# BATTERIES_CONTROLLER.net
KiCad netlist of a schematic drawn in EAGLE
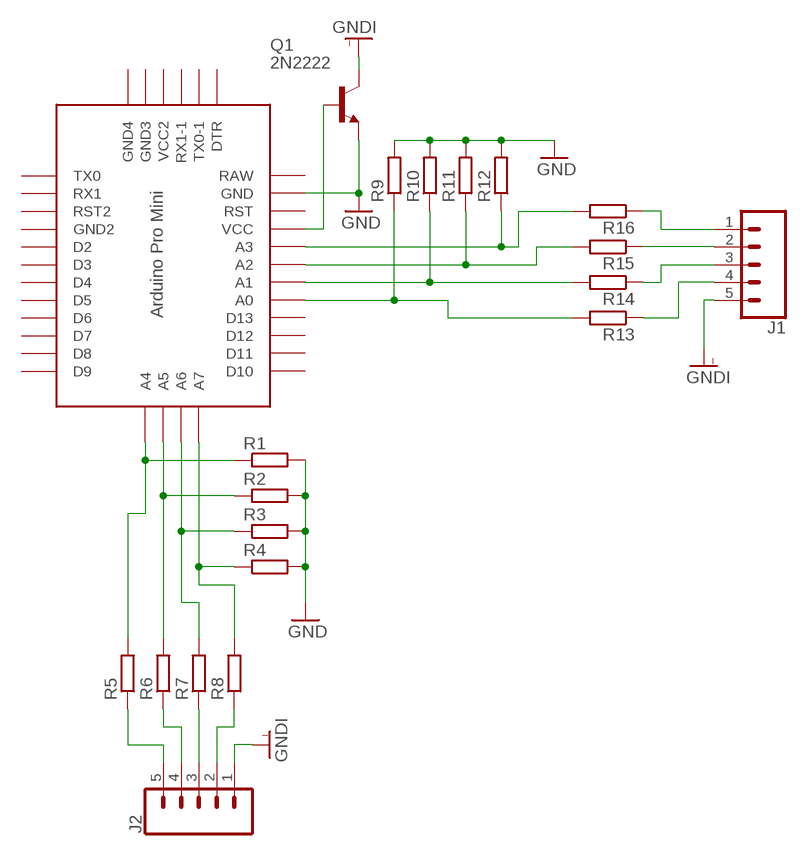
[diagram p0: schematic, sheet 1]

(export (version "E")
  (design (tool "Eeschema 10.0.6"))
  (components
    (comp (ref "J1")
      (value "CONN_05")
      (footprint "eagle-import:1X05")
      (libsource (lib "eagle-import") (part "CONN_05"))
    )
    (comp (ref "J2")
      (value "CONN_05")
      (footprint "eagle-import:1X05")
      (libsource (lib "eagle-import") (part "CONN_05"))
    )
    (comp (ref "Q1")
      (value "2N2222")
      (footprint "eagle-import:TO18")
      (libsource (lib "eagle-import") (part "2N2222"))
    )
    (comp (ref "R1")
      (value "R-EU_0204/7")
      (footprint "eagle-import:0204_7")
      (libsource (lib "eagle-import") (part "R-EU_0204/7"))
    )
    (comp (ref "R2")
      (value "R-EU_0204/7")
      (footprint "eagle-import:0204_7")
      (libsource (lib "eagle-import") (part "R-EU_0204/7"))
    )
    (comp (ref "R3")
      (value "R-EU_0204/7")
      (footprint "eagle-import:0204_7")
      (libsource (lib "eagle-import") (part "R-EU_0204/7"))
    )
    (comp (ref "R4")
      (value "R-EU_0204/7")
      (footprint "eagle-import:0204_7")
      (libsource (lib "eagle-import") (part "R-EU_0204/7"))
    )
    (comp (ref "R5")
      (value "R-EU_0204/7")
      (footprint "eagle-import:0204_7")
      (libsource (lib "eagle-import") (part "R-EU_0204/7"))
    )
    (comp (ref "R6")
      (value "R-EU_0204/7")
      (footprint "eagle-import:0204_7")
      (libsource (lib "eagle-import") (part "R-EU_0204/7"))
    )
    (comp (ref "R7")
      (value "R-EU_0204/7")
      (footprint "eagle-import:0204_7")
      (libsource (lib "eagle-import") (part "R-EU_0204/7"))
    )
    (comp (ref "R8")
      (value "R-EU_0204/7")
      (footprint "eagle-import:0204_7")
      (libsource (lib "eagle-import") (part "R-EU_0204/7"))
    )
    (comp (ref "R9")
      (value "R-EU_0204/7")
      (footprint "eagle-import:0204_7")
      (libsource (lib "eagle-import") (part "R-EU_0204/7"))
    )
    (comp (ref "R10")
      (value "R-EU_0204/7")
      (footprint "eagle-import:0204_7")
      (libsource (lib "eagle-import") (part "R-EU_0204/7"))
    )
    (comp (ref "R11")
      (value "R-EU_0204/7")
      (footprint "eagle-import:0204_7")
      (libsource (lib "eagle-import") (part "R-EU_0204/7"))
    )
    (comp (ref "R12")
      (value "R-EU_0207/10")
      (footprint "eagle-import:0207_10")
      (libsource (lib "eagle-import") (part "R-EU_0207/10"))
    )
    (comp (ref "R13")
      (value "R-EU_0204/7")
      (footprint "eagle-import:0204_7")
      (libsource (lib "eagle-import") (part "R-EU_0204/7"))
    )
    (comp (ref "R14")
      (value "R-EU_0204/7")
      (footprint "eagle-import:0204_7")
      (libsource (lib "eagle-import") (part "R-EU_0204/7"))
    )
    (comp (ref "R15")
      (value "R-EU_0204/7")
      (footprint "eagle-import:0204_7")
      (libsource (lib "eagle-import") (part "R-EU_0204/7"))
    )
    (comp (ref "R16")
      (value "R-EU_0204/7")
      (footprint "eagle-import:0204_7")
      (libsource (lib "eagle-import") (part "R-EU_0204/7"))
    )
    (comp (ref "U$1")
      (value "PRO-MINI")
      (footprint "eagle-import:PRO-MINI")
      (libsource (lib "eagle-import") (part "PRO-MINI"))
    )
  )
  (nets
    (net (code "1") (name "/RAW") (class "Default")
      (node (ref "U$1") (pin "RAW") (pinfunction "RAW_RAW") (pintype "power_in"))
    )
    (net (code "2") (name "GND") (class "Default")
      (node (ref "Q1") (pin "1") (pinfunction "E_1") (pintype "passive"))
      (node (ref "R1") (pin "2") (pinfunction "2_2") (pintype "passive"))
      (node (ref "R10") (pin "2") (pinfunction "2_2") (pintype "passive"))
      (node (ref "R11") (pin "2") (pinfunction "2_2") (pintype "passive"))
      (node (ref "R12") (pin "2") (pinfunction "2_2") (pintype "passive"))
      (node (ref "R2") (pin "2") (pinfunction "2_2") (pintype "passive"))
      (node (ref "R3") (pin "2") (pinfunction "2_2") (pintype "passive"))
      (node (ref "R4") (pin "2") (pinfunction "2_2") (pintype "passive"))
      (node (ref "R9") (pin "2") (pinfunction "2_2") (pintype "passive"))
      (node (ref "U$1") (pin "GND") (pinfunction "GND_GND") (pintype "input"))
    )
    (net (code "3") (name "GNDI") (class "Default")
      (node (ref "J1") (pin "5") (pinfunction "5_5") (pintype "passive"))
      (node (ref "J2") (pin "1") (pinfunction "1_1") (pintype "passive"))
      (node (ref "Q1") (pin "3") (pinfunction "C_3") (pintype "passive"))
    )
    (net (code "4") (name "Net-(J1-Pad1)") (class "Default")
      (node (ref "J1") (pin "1") (pinfunction "1_1") (pintype "passive"))
      (node (ref "R16") (pin "1") (pinfunction "1_1") (pintype "passive"))
    )
    (net (code "5") (name "Net-(J1-Pad2)") (class "Default")
      (node (ref "J1") (pin "2") (pinfunction "2_2") (pintype "passive"))
      (node (ref "R15") (pin "1") (pinfunction "1_1") (pintype "passive"))
    )
    (net (code "6") (name "Net-(J1-Pad3)") (class "Default")
      (node (ref "J1") (pin "3") (pinfunction "3_3") (pintype "passive"))
      (node (ref "R14") (pin "1") (pinfunction "1_1") (pintype "passive"))
    )
    (net (code "7") (name "Net-(J1-Pad4)") (class "Default")
      (node (ref "J1") (pin "4") (pinfunction "4_4") (pintype "passive"))
      (node (ref "R13") (pin "1") (pinfunction "1_1") (pintype "passive"))
    )
    (net (code "8") (name "Net-(J2-Pad2)") (class "Default")
      (node (ref "J2") (pin "2") (pinfunction "2_2") (pintype "passive"))
      (node (ref "R8") (pin "1") (pinfunction "1_1") (pintype "passive"))
    )
    (net (code "9") (name "Net-(J2-Pad3)") (class "Default")
      (node (ref "J2") (pin "3") (pinfunction "3_3") (pintype "passive"))
      (node (ref "R7") (pin "1") (pinfunction "1_1") (pintype "passive"))
    )
    (net (code "10") (name "Net-(J2-Pad4)") (class "Default")
      (node (ref "J2") (pin "4") (pinfunction "4_4") (pintype "passive"))
      (node (ref "R6") (pin "1") (pinfunction "1_1") (pintype "passive"))
    )
    (net (code "11") (name "Net-(J2-Pad5)") (class "Default")
      (node (ref "J2") (pin "5") (pinfunction "5_5") (pintype "passive"))
      (node (ref "R5") (pin "1") (pinfunction "1_1") (pintype "passive"))
    )
    (net (code "12") (name "Net-(Q1-B)") (class "Default")
      (node (ref "Q1") (pin "2") (pinfunction "B_2") (pintype "passive"))
      (node (ref "U$1") (pin "VCC") (pinfunction "VCC_VCC") (pintype "bidirectional"))
    )
    (net (code "13") (name "Net-(R1-Pad1)") (class "Default")
      (node (ref "R1") (pin "1") (pinfunction "1_1") (pintype "passive"))
      (node (ref "R5") (pin "2") (pinfunction "2_2") (pintype "passive"))
      (node (ref "U$1") (pin "A4") (pinfunction "A4_A4") (pintype "bidirectional"))
    )
    (net (code "14") (name "Net-(R2-Pad1)") (class "Default")
      (node (ref "R2") (pin "1") (pinfunction "1_1") (pintype "passive"))
      (node (ref "R6") (pin "2") (pinfunction "2_2") (pintype "passive"))
      (node (ref "U$1") (pin "A5") (pinfunction "A5_A5") (pintype "bidirectional"))
    )
    (net (code "15") (name "Net-(R3-Pad1)") (class "Default")
      (node (ref "R3") (pin "1") (pinfunction "1_1") (pintype "passive"))
      (node (ref "R7") (pin "2") (pinfunction "2_2") (pintype "passive"))
      (node (ref "U$1") (pin "A6") (pinfunction "A6_A6") (pintype "bidirectional"))
    )
    (net (code "16") (name "Net-(R4-Pad1)") (class "Default")
      (node (ref "R4") (pin "1") (pinfunction "1_1") (pintype "passive"))
      (node (ref "R8") (pin "2") (pinfunction "2_2") (pintype "passive"))
      (node (ref "U$1") (pin "A7") (pinfunction "A7_A7") (pintype "bidirectional"))
    )
    (net (code "17") (name "Net-(R10-Pad1)") (class "Default")
      (node (ref "R10") (pin "1") (pinfunction "1_1") (pintype "passive"))
      (node (ref "R14") (pin "2") (pinfunction "2_2") (pintype "passive"))
      (node (ref "U$1") (pin "A1") (pinfunction "A1_A1") (pintype "bidirectional"))
    )
    (net (code "18") (name "Net-(R11-Pad1)") (class "Default")
      (node (ref "R11") (pin "1") (pinfunction "1_1") (pintype "passive"))
      (node (ref "R15") (pin "2") (pinfunction "2_2") (pintype "passive"))
      (node (ref "U$1") (pin "A2") (pinfunction "A2_A2") (pintype "bidirectional"))
    )
    (net (code "19") (name "Net-(R12-Pad1)") (class "Default")
      (node (ref "R12") (pin "1") (pinfunction "1_1") (pintype "passive"))
      (node (ref "R16") (pin "2") (pinfunction "2_2") (pintype "passive"))
      (node (ref "U$1") (pin "A3") (pinfunction "A3_A3") (pintype "bidirectional"))
    )
    (net (code "20") (name "Net-(R13-Pad2)") (class "Default")
      (node (ref "R13") (pin "2") (pinfunction "2_2") (pintype "passive"))
      (node (ref "R9") (pin "1") (pinfunction "1_1") (pintype "passive"))
      (node (ref "U$1") (pin "A0") (pinfunction "A0_A0") (pintype "bidirectional"))
    )
    (net (code "21") (name "unconnected-(U$1-GND2-PadGND1)") (class "Default")
      (node (ref "U$1") (pin "GND1") (pinfunction "GND2_GND1") (pintype "bidirectional"))
    )
    (net (code "22") (name "unconnected-(U$1-GND4-PadGND2)") (class "Default")
      (node (ref "U$1") (pin "GND2") (pinfunction "GND4_GND2") (pintype "bidirectional"))
    )
    (net (code "23") (name "unconnected-(U$1-PadD2)") (class "Default")
      (node (ref "U$1") (pin "D2") (pinfunction "D2_D2") (pintype "bidirectional"))
    )
    (net (code "24") (name "unconnected-(U$1-PadD3)") (class "Default")
      (node (ref "U$1") (pin "D3") (pinfunction "D3_D3") (pintype "bidirectional"))
    )
    (net (code "25") (name "unconnected-(U$1-PadD4)") (class "Default")
      (node (ref "U$1") (pin "D4") (pinfunction "D4_D4") (pintype "bidirectional"))
    )
    (net (code "26") (name "unconnected-(U$1-PadD5)") (class "Default")
      (node (ref "U$1") (pin "D5") (pinfunction "D5_D5") (pintype "bidirectional"))
    )
    (net (code "27") (name "unconnected-(U$1-PadD6)") (class "Default")
      (node (ref "U$1") (pin "D6") (pinfunction "D6_D6") (pintype "bidirectional"))
    )
    (net (code "28") (name "unconnected-(U$1-PadD7)") (class "Default")
      (node (ref "U$1") (pin "D7") (pinfunction "D7_D7") (pintype "bidirectional"))
    )
    (net (code "29") (name "unconnected-(U$1-PadD8)") (class "Default")
      (node (ref "U$1") (pin "D8") (pinfunction "D8_D8") (pintype "bidirectional"))
    )
    (net (code "30") (name "unconnected-(U$1-PadD9)") (class "Default")
      (node (ref "U$1") (pin "D9") (pinfunction "D9_D9") (pintype "bidirectional"))
    )
    (net (code "31") (name "unconnected-(U$1-PadD10)") (class "Default")
      (node (ref "U$1") (pin "D10") (pinfunction "D10_D10") (pintype "bidirectional"))
    )
    (net (code "32") (name "unconnected-(U$1-PadD11)") (class "Default")
      (node (ref "U$1") (pin "D11") (pinfunction "D11_D11") (pintype "bidirectional"))
    )
    (net (code "33") (name "unconnected-(U$1-PadD12)") (class "Default")
      (node (ref "U$1") (pin "D12") (pinfunction "D12_D12") (pintype "bidirectional"))
    )
    (net (code "34") (name "unconnected-(U$1-PadD13)") (class "Default")
      (node (ref "U$1") (pin "D13") (pinfunction "D13_D13") (pintype "bidirectional"))
    )
    (net (code "35") (name "unconnected-(U$1-PadDTR)") (class "Default")
      (node (ref "U$1") (pin "DTR") (pinfunction "DTR_DTR") (pintype "bidirectional"))
    )
    (net (code "36") (name "unconnected-(U$1-PadGND3)") (class "Default")
      (node (ref "U$1") (pin "GND3") (pinfunction "GND3_GND3") (pintype "bidirectional"))
    )
    (net (code "37") (name "unconnected-(U$1-PadRST)") (class "Default")
      (node (ref "U$1") (pin "RST") (pinfunction "RST_RST") (pintype "bidirectional"))
    )
    (net (code "38") (name "unconnected-(U$1-PadRX1)") (class "Default")
      (node (ref "U$1") (pin "RX1") (pinfunction "RX1_RX1") (pintype "bidirectional"))
    )
    (net (code "39") (name "unconnected-(U$1-PadRX1-1)") (class "Default")
      (node (ref "U$1") (pin "RX1-1") (pinfunction "RX1-1_RX1-1") (pintype "bidirectional"))
    )
    (net (code "40") (name "unconnected-(U$1-PadTX0)") (class "Default")
      (node (ref "U$1") (pin "TX0") (pinfunction "TX0_TX0") (pintype "bidirectional"))
    )
    (net (code "41") (name "unconnected-(U$1-PadTX0-1)") (class "Default")
      (node (ref "U$1") (pin "TX0-1") (pinfunction "TX0-1_TX0-1") (pintype "bidirectional"))
    )
    (net (code "42") (name "unconnected-(U$1-RST2-PadRST1)") (class "Default")
      (node (ref "U$1") (pin "RST1") (pinfunction "RST2_RST1") (pintype "bidirectional"))
    )
    (net (code "43") (name "unconnected-(U$1-VCC2-PadVCC1)") (class "Default")
      (node (ref "U$1") (pin "VCC1") (pinfunction "VCC2_VCC1") (pintype "bidirectional"))
    )
  )
)
